# MK2.net
KiCad netlist of a schematic drawn in Altium Designer
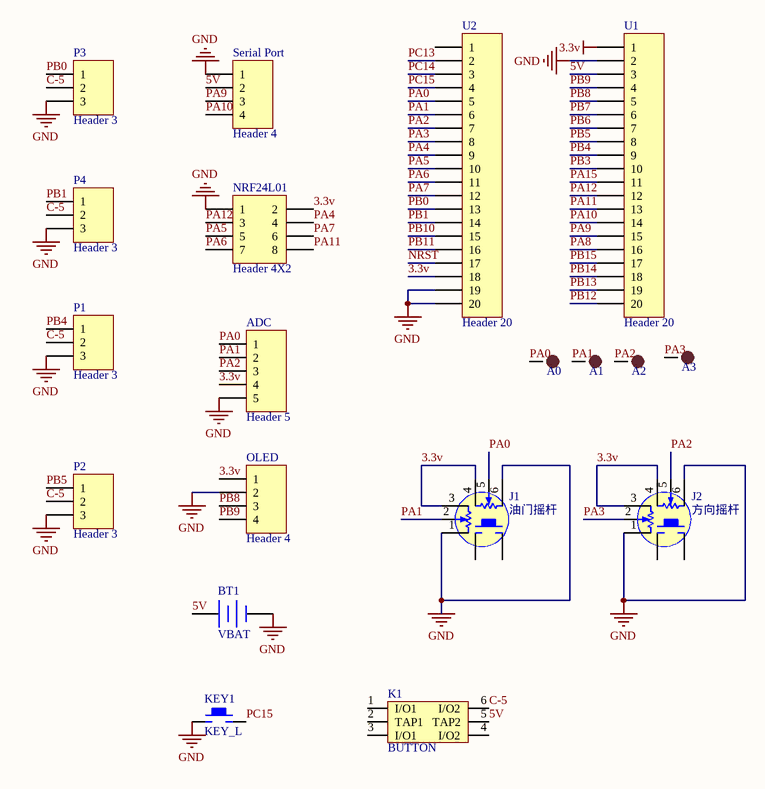
[diagram p0: MK2.SchDoc]

(export (version "E")
  (design (tool "Eeschema 10.0.6"))
  (components
    (comp (ref "A0")
      (value "TEST POINT")
      (footprint "TP-1.5")
      (description "测试点")
      (libsource (lib "战舰STM32开发板底板封装库") (part "TEST-POINT"))
    )
    (comp (ref "A1")
      (value "TEST POINT")
      (footprint "TP-1.5")
      (description "测试点")
      (libsource (lib "战舰STM32开发板底板封装库") (part "TEST-POINT"))
    )
    (comp (ref "A2")
      (value "TEST POINT")
      (footprint "TP-1.5")
      (description "测试点")
      (libsource (lib "战舰STM32开发板底板封装库") (part "TEST-POINT"))
    )
    (comp (ref "A3")
      (value "TEST POINT")
      (footprint "TP-1.5")
      (description "测试点")
      (libsource (lib "战舰STM32开发板底板封装库") (part "TEST-POINT"))
    )
    (comp (ref "ADC")
      (value "Header 5")
      (footprint "HDR1X5")
      (description "Header, 5-Pin")
      (fields (field (name "PUBLISHER") "Altium Limited"))
      (libsource (lib "Miscellaneous Connectors") (part "Header 5"))
    )
    (comp (ref "BT1")
      (value "VBAT")
      (footprint "BAT-2")
      (description "Multicell Battery")
      (fields (field (name "PUBLISHER") "Altium Limited"))
      (libsource (lib "REMOTOR V1.6") (part "Battery"))
    )
    (comp (ref "J1")
      (value "油门摇杆")
      (footprint "摇杆2")
      (description "摇杆")
      (libsource (lib "REMOTOR V1.6") (part "摇杆"))
    )
    (comp (ref "J2")
      (value "方向摇杆")
      (footprint "摇杆2")
      (description "摇杆")
      (libsource (lib "REMOTOR V1.6") (part "摇杆_1"))
    )
    (comp (ref "K1")
      (value "BUTTON")
      (footprint "BTN8.5*8.5")
      (libsource (lib "战舰STM32开发板底板封装库") (part "BUTTON"))
    )
    (comp (ref "KEY1") (value "KEY_L") (footprint "KEY_M") (libsource (lib "REMOTOR V1.6") (part "KEY")))
    (comp (ref "NRF24L01")
      (value "Header 4X2")
      (footprint "HDR2X4")
      (description "Header, 4-Pin, Dual row")
      (fields (field (name "PUBLISHER") "Altium Limited"))
      (libsource (lib "Miscellaneous Connectors") (part "Header 4X2"))
    )
    (comp (ref "OLED")
      (value "Header 4")
      (footprint "HDR1X4")
      (description "Header, 4-Pin")
      (fields (field (name "PUBLISHER") "Altium Limited"))
      (libsource (lib "Miscellaneous Connectors") (part "Header 4"))
    )
    (comp (ref "P1")
      (value "Header 3")
      (footprint "HDR1X3")
      (description "Header, 3-Pin")
      (fields (field (name "PUBLISHER") "Altium Limited"))
      (libsource (lib "Miscellaneous Connectors") (part "Header 3"))
    )
    (comp (ref "P2")
      (value "Header 3")
      (footprint "HDR1X3")
      (description "Header, 3-Pin")
      (fields (field (name "PUBLISHER") "Altium Limited"))
      (libsource (lib "Miscellaneous Connectors") (part "Header 3"))
    )
    (comp (ref "P3")
      (value "Header 3")
      (footprint "HDR1X3")
      (description "Header, 3-Pin")
      (fields (field (name "PUBLISHER") "Altium Limited"))
      (libsource (lib "Miscellaneous Connectors") (part "Header 3"))
    )
    (comp (ref "P4")
      (value "Header 3")
      (footprint "HDR1X3")
      (description "Header, 3-Pin")
      (fields (field (name "PUBLISHER") "Altium Limited"))
      (libsource (lib "Miscellaneous Connectors") (part "Header 3"))
    )
    (comp (ref "Serial Port")
      (value "Header 4")
      (footprint "HDR1X4")
      (description "Header, 4-Pin")
      (fields (field (name "PUBLISHER") "Altium Limited"))
      (libsource (lib "Miscellaneous Connectors") (part "Header 4"))
    )
    (comp (ref "U1")
      (value "Header 20")
      (footprint "HDR1X20")
      (description "Header, 20-Pin")
      (fields (field (name "PUBLISHER") "Altium Limited"))
      (libsource (lib "Miscellaneous Connectors") (part "Header 20"))
    )
    (comp (ref "U2")
      (value "Header 20")
      (footprint "HDR1X20")
      (description "Header, 20-Pin")
      (fields (field (name "PUBLISHER") "Altium Limited"))
      (libsource (lib "Miscellaneous Connectors") (part "Header 20"))
    )
  )
  (nets
    (net (code "1") (name "/5V") (class "Default")
      (node (ref "BT1") (pin "1") (pinfunction "+_1") (pintype "passive"))
      (node (ref "K1") (pin "5") (pinfunction "TAP2_5") (pintype "passive"))
      (node (ref "Serial Port") (pin "2") (pinfunction "2_2") (pintype "passive"))
      (node (ref "U1") (pin "3") (pinfunction "3_3") (pintype "passive"))
    )
    (net (code "2") (name "/C-5") (class "Default")
      (node (ref "K1") (pin "6") (pinfunction "I/O2_6") (pintype "passive"))
      (node (ref "P1") (pin "2") (pinfunction "2_2") (pintype "passive"))
      (node (ref "P2") (pin "2") (pinfunction "2_2") (pintype "passive"))
      (node (ref "P3") (pin "2") (pinfunction "2_2") (pintype "passive"))
      (node (ref "P4") (pin "2") (pinfunction "2_2") (pintype "passive"))
    )
    (net (code "3") (name "/NRST") (class "Default")
      (node (ref "U2") (pin "17") (pinfunction "17_17") (pintype "passive"))
    )
    (net (code "4") (name "/PA0") (class "Default")
      (node (ref "A0") (pin "1") (pinfunction "1_1") (pintype "passive"))
      (node (ref "ADC") (pin "1") (pinfunction "1_1") (pintype "passive"))
      (node (ref "J1") (pin "5") (pinfunction "5_5") (pintype "passive"))
      (node (ref "U2") (pin "5") (pinfunction "5_5") (pintype "passive"))
    )
    (net (code "5") (name "/PA1") (class "Default")
      (node (ref "A1") (pin "1") (pinfunction "1_1") (pintype "passive"))
      (node (ref "ADC") (pin "2") (pinfunction "2_2") (pintype "passive"))
      (node (ref "J1") (pin "2") (pinfunction "2_2") (pintype "passive"))
      (node (ref "U2") (pin "6") (pinfunction "6_6") (pintype "passive"))
    )
    (net (code "6") (name "/PA2") (class "Default")
      (node (ref "A2") (pin "1") (pinfunction "1_1") (pintype "passive"))
      (node (ref "ADC") (pin "3") (pinfunction "3_3") (pintype "passive"))
      (node (ref "J2") (pin "5") (pinfunction "5_5") (pintype "passive"))
      (node (ref "U2") (pin "7") (pinfunction "7_7") (pintype "passive"))
    )
    (net (code "7") (name "/PA3") (class "Default")
      (node (ref "A3") (pin "1") (pinfunction "1_1") (pintype "passive"))
      (node (ref "J2") (pin "2") (pinfunction "2_2") (pintype "passive"))
      (node (ref "U2") (pin "8") (pinfunction "8_8") (pintype "passive"))
    )
    (net (code "8") (name "/PA4") (class "Default")
      (node (ref "NRF24L01") (pin "4") (pinfunction "4_4") (pintype "passive"))
      (node (ref "U2") (pin "9") (pinfunction "9_9") (pintype "passive"))
    )
    (net (code "9") (name "/PA5") (class "Default")
      (node (ref "NRF24L01") (pin "5") (pinfunction "5_5") (pintype "passive"))
      (node (ref "U2") (pin "10") (pinfunction "10_10") (pintype "passive"))
    )
    (net (code "10") (name "/PA6") (class "Default")
      (node (ref "NRF24L01") (pin "7") (pinfunction "7_7") (pintype "passive"))
      (node (ref "U2") (pin "11") (pinfunction "11_11") (pintype "passive"))
    )
    (net (code "11") (name "/PA7") (class "Default")
      (node (ref "NRF24L01") (pin "6") (pinfunction "6_6") (pintype "passive"))
      (node (ref "U2") (pin "12") (pinfunction "12_12") (pintype "passive"))
    )
    (net (code "12") (name "/PA8") (class "Default")
      (node (ref "U1") (pin "16") (pinfunction "16_16") (pintype "passive"))
    )
    (net (code "13") (name "/PA9") (class "Default")
      (node (ref "Serial Port") (pin "3") (pinfunction "3_3") (pintype "passive"))
      (node (ref "U1") (pin "15") (pinfunction "15_15") (pintype "passive"))
    )
    (net (code "14") (name "/PA10") (class "Default")
      (node (ref "Serial Port") (pin "4") (pinfunction "4_4") (pintype "passive"))
      (node (ref "U1") (pin "14") (pinfunction "14_14") (pintype "passive"))
    )
    (net (code "15") (name "/PA11") (class "Default")
      (node (ref "NRF24L01") (pin "8") (pinfunction "8_8") (pintype "passive"))
      (node (ref "U1") (pin "13") (pinfunction "13_13") (pintype "passive"))
    )
    (net (code "16") (name "/PA12") (class "Default")
      (node (ref "NRF24L01") (pin "3") (pinfunction "3_3") (pintype "passive"))
      (node (ref "U1") (pin "12") (pinfunction "12_12") (pintype "passive"))
    )
    (net (code "17") (name "/PA15") (class "Default")
      (node (ref "U1") (pin "11") (pinfunction "11_11") (pintype "passive"))
    )
    (net (code "18") (name "/PB0") (class "Default")
      (node (ref "P3") (pin "1") (pinfunction "1_1") (pintype "passive"))
      (node (ref "U2") (pin "13") (pinfunction "13_13") (pintype "passive"))
    )
    (net (code "19") (name "/PB1") (class "Default")
      (node (ref "P4") (pin "1") (pinfunction "1_1") (pintype "passive"))
      (node (ref "U2") (pin "14") (pinfunction "14_14") (pintype "passive"))
    )
    (net (code "20") (name "/PB3") (class "Default")
      (node (ref "U1") (pin "10") (pinfunction "10_10") (pintype "passive"))
    )
    (net (code "21") (name "/PB4") (class "Default")
      (node (ref "P1") (pin "1") (pinfunction "1_1") (pintype "passive"))
      (node (ref "U1") (pin "9") (pinfunction "9_9") (pintype "passive"))
    )
    (net (code "22") (name "/PB5") (class "Default")
      (node (ref "P2") (pin "1") (pinfunction "1_1") (pintype "passive"))
      (node (ref "U1") (pin "8") (pinfunction "8_8") (pintype "passive"))
    )
    (net (code "23") (name "/PB6") (class "Default")
      (node (ref "U1") (pin "7") (pinfunction "7_7") (pintype "passive"))
    )
    (net (code "24") (name "/PB7") (class "Default")
      (node (ref "U1") (pin "6") (pinfunction "6_6") (pintype "passive"))
    )
    (net (code "25") (name "/PB8") (class "Default")
      (node (ref "OLED") (pin "3") (pinfunction "3_3") (pintype "passive"))
      (node (ref "U1") (pin "5") (pinfunction "5_5") (pintype "passive"))
    )
    (net (code "26") (name "/PB9") (class "Default")
      (node (ref "OLED") (pin "4") (pinfunction "4_4") (pintype "passive"))
      (node (ref "U1") (pin "4") (pinfunction "4_4") (pintype "passive"))
    )
    (net (code "27") (name "/PB10") (class "Default")
      (node (ref "U2") (pin "15") (pinfunction "15_15") (pintype "passive"))
    )
    (net (code "28") (name "/PB11") (class "Default")
      (node (ref "U2") (pin "16") (pinfunction "16_16") (pintype "passive"))
    )
    (net (code "29") (name "/PB12") (class "Default")
      (node (ref "U1") (pin "20") (pinfunction "20_20") (pintype "passive"))
    )
    (net (code "30") (name "/PB13") (class "Default")
      (node (ref "U1") (pin "19") (pinfunction "19_19") (pintype "passive"))
    )
    (net (code "31") (name "/PB14") (class "Default")
      (node (ref "U1") (pin "18") (pinfunction "18_18") (pintype "passive"))
    )
    (net (code "32") (name "/PB15") (class "Default")
      (node (ref "U1") (pin "17") (pinfunction "17_17") (pintype "passive"))
    )
    (net (code "33") (name "/PC13") (class "Default")
      (node (ref "U2") (pin "2") (pinfunction "2_2") (pintype "passive"))
    )
    (net (code "34") (name "/PC14") (class "Default")
      (node (ref "U2") (pin "3") (pinfunction "3_3") (pintype "passive"))
    )
    (net (code "35") (name "/PC15") (class "Default")
      (node (ref "KEY1") (pin "2") (pinfunction "2_2") (pintype "passive"))
      (node (ref "U2") (pin "4") (pinfunction "4_4") (pintype "passive"))
    )
    (net (code "36") (name "3.3v") (class "Default")
      (node (ref "ADC") (pin "4") (pinfunction "4_4") (pintype "passive"))
      (node (ref "J1") (pin "3") (pinfunction "3_3") (pintype "passive"))
      (node (ref "J1") (pin "4") (pinfunction "4_4") (pintype "passive"))
      (node (ref "J2") (pin "3") (pinfunction "3_3") (pintype "passive"))
      (node (ref "J2") (pin "4") (pinfunction "4_4") (pintype "passive"))
      (node (ref "NRF24L01") (pin "2") (pinfunction "2_2") (pintype "passive"))
      (node (ref "OLED") (pin "1") (pinfunction "1_1") (pintype "passive"))
      (node (ref "U1") (pin "1") (pinfunction "1_1") (pintype "passive"))
      (node (ref "U2") (pin "18") (pinfunction "18_18") (pintype "passive"))
    )
    (net (code "37") (name "GND") (class "Default")
      (node (ref "ADC") (pin "5") (pinfunction "5_5") (pintype "passive"))
      (node (ref "BT1") (pin "2") (pinfunction "-_2") (pintype "passive"))
      (node (ref "J1") (pin "1") (pinfunction "1_1") (pintype "passive"))
      (node (ref "J1") (pin "6") (pinfunction "6_6") (pintype "passive"))
      (node (ref "J2") (pin "1") (pinfunction "1_1") (pintype "passive"))
      (node (ref "J2") (pin "6") (pinfunction "6_6") (pintype "passive"))
      (node (ref "KEY1") (pin "1") (pinfunction "1_1") (pintype "passive"))
      (node (ref "NRF24L01") (pin "1") (pinfunction "1_1") (pintype "passive"))
      (node (ref "OLED") (pin "2") (pinfunction "2_2") (pintype "passive"))
      (node (ref "P1") (pin "3") (pinfunction "3_3") (pintype "passive"))
      (node (ref "P2") (pin "3") (pinfunction "3_3") (pintype "passive"))
      (node (ref "P3") (pin "3") (pinfunction "3_3") (pintype "passive"))
      (node (ref "P4") (pin "3") (pinfunction "3_3") (pintype "passive"))
      (node (ref "Serial Port") (pin "1") (pinfunction "1_1") (pintype "passive"))
      (node (ref "U1") (pin "2") (pinfunction "2_2") (pintype "passive"))
      (node (ref "U2") (pin "19") (pinfunction "19_19") (pintype "passive"))
      (node (ref "U2") (pin "20") (pinfunction "20_20") (pintype "passive"))
    )
    (net (code "38") (name "unconnected-(J1-PadJ1)") (class "Default")
      (node (ref "J1") (pin "J1") (pinfunction "J1_J1") (pintype "passive"))
    )
    (net (code "39") (name "unconnected-(J1-PadJ2)") (class "Default")
      (node (ref "J1") (pin "J2") (pinfunction "J2_J2") (pintype "passive"))
    )
    (net (code "40") (name "unconnected-(J2-PadJ1)") (class "Default")
      (node (ref "J2") (pin "J1") (pinfunction "J1_J1") (pintype "passive"))
    )
    (net (code "41") (name "unconnected-(J2-PadJ2)") (class "Default")
      (node (ref "J2") (pin "J2") (pinfunction "J2_J2") (pintype "passive"))
    )
    (net (code "42") (name "unconnected-(K1-I{slash}O1-Pad1)") (class "Default")
      (node (ref "K1") (pin "1") (pinfunction "I/O1_1") (pintype "passive"))
    )
    (net (code "43") (name "unconnected-(K1-I{slash}O1-Pad3)") (class "Default")
      (node (ref "K1") (pin "3") (pinfunction "I/O1_3") (pintype "passive"))
    )
    (net (code "44") (name "unconnected-(K1-I{slash}O2-Pad4)") (class "Default")
      (node (ref "K1") (pin "4") (pinfunction "I/O2_4") (pintype "passive"))
    )
    (net (code "45") (name "unconnected-(K1-TAP1-Pad2)") (class "Default")
      (node (ref "K1") (pin "2") (pinfunction "TAP1_2") (pintype "passive"))
    )
    (net (code "46") (name "unconnected-(U2-Pad1)") (class "Default")
      (node (ref "U2") (pin "1") (pinfunction "1_1") (pintype "passive"))
    )
  )
)
